# EPWR01.net
KiCad netlist of a schematic drawn in EAGLE
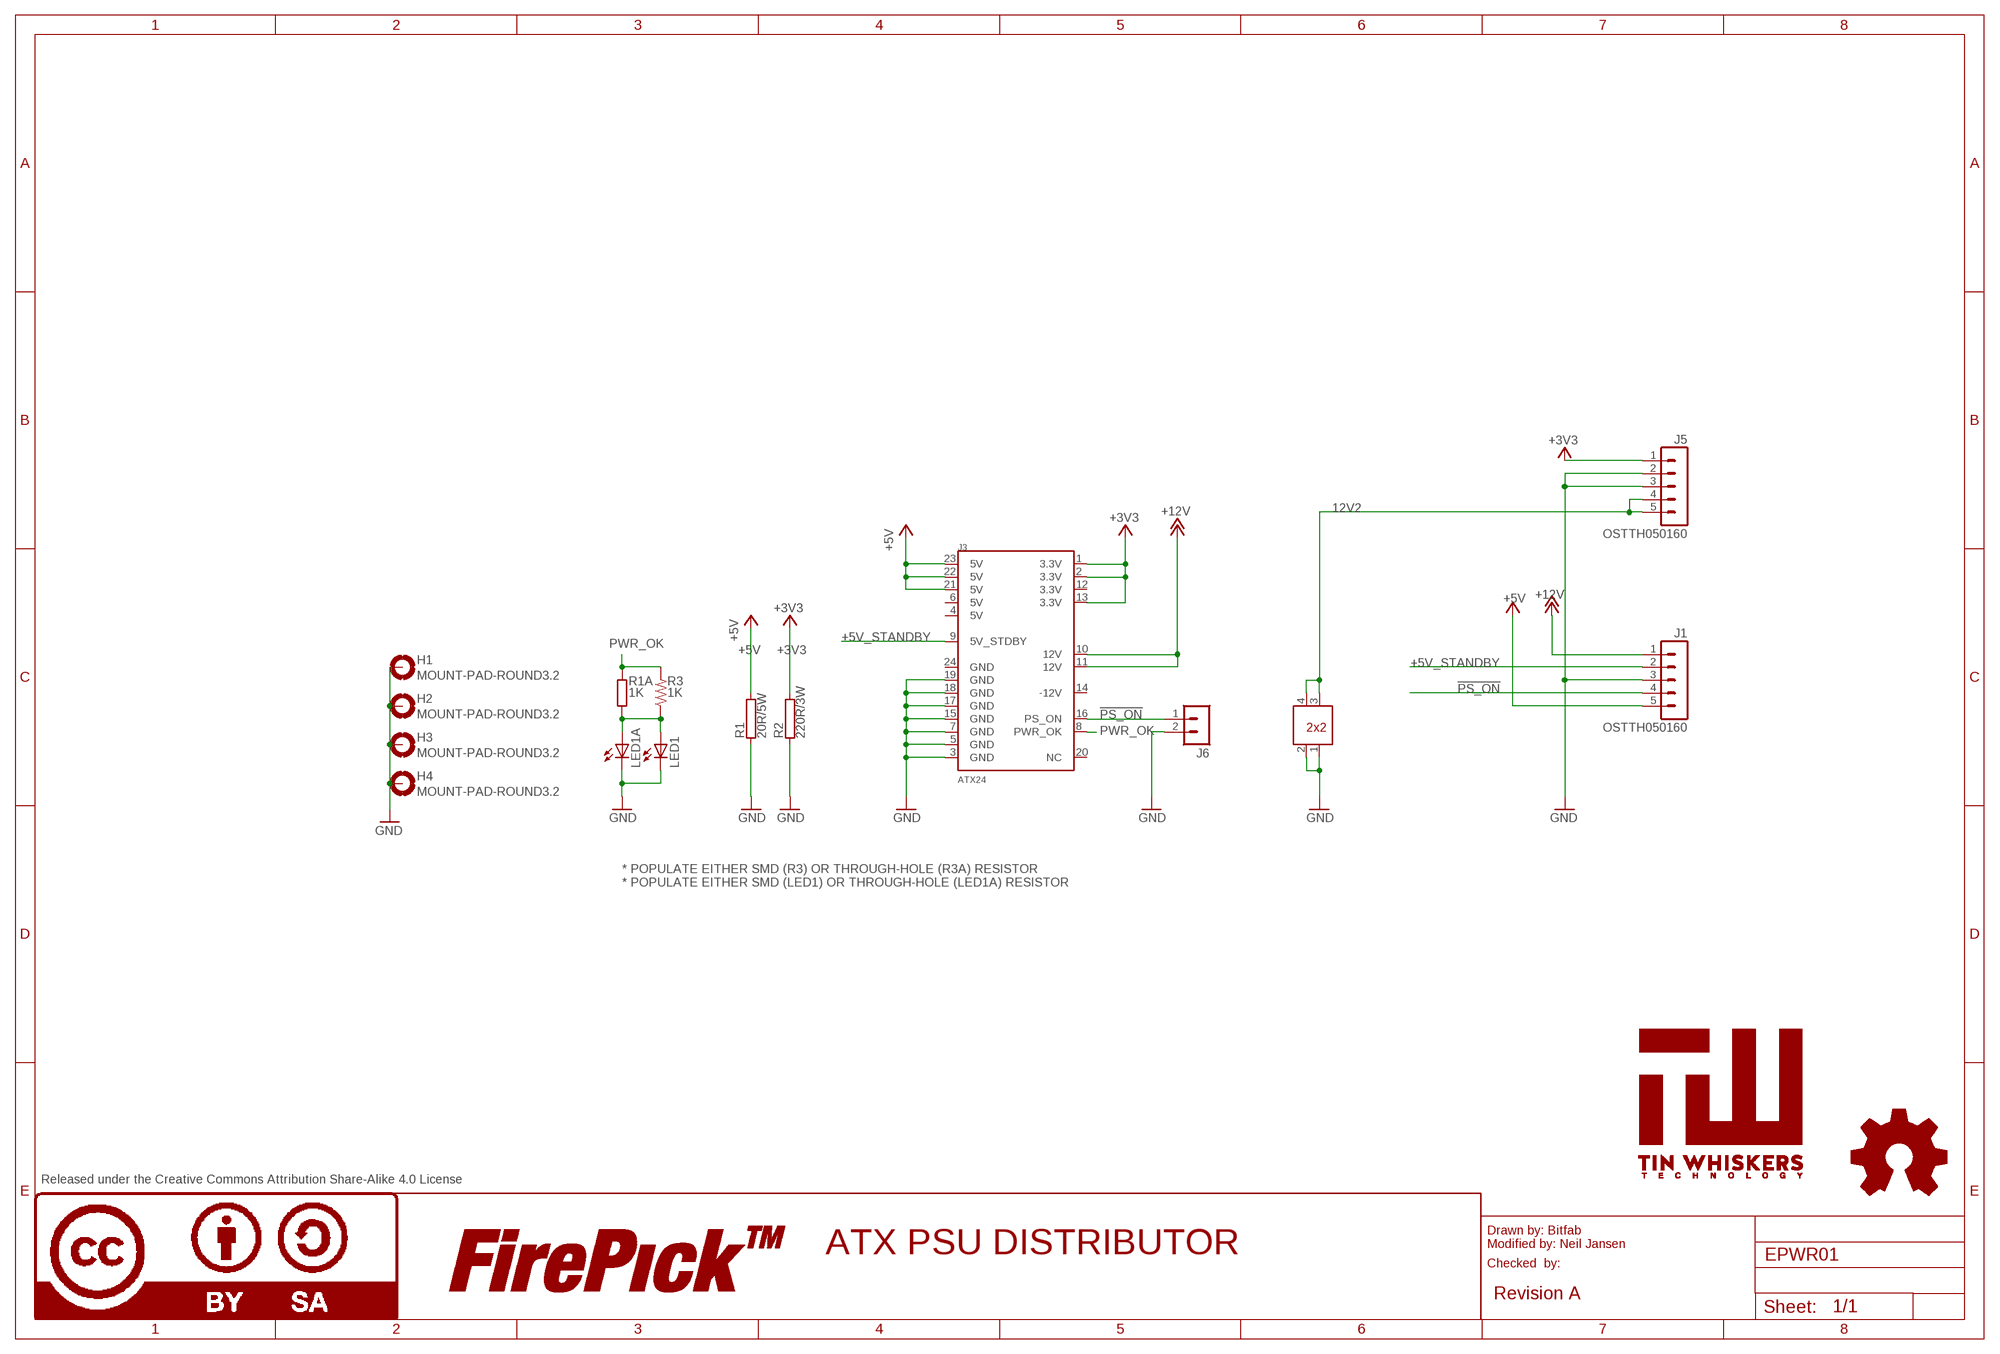
[diagram p0: schematic, sheet 1]

(export (version "E")
  (design (tool "Eeschema 10.0.6"))
  (components
    (comp (ref "H1")
      (value "MOUNT-PAD-ROUND3.2")
      (footprint "eagle-import:3,2-PAD")
      (libsource (lib "eagle-import") (part "MOUNT-PAD-ROUND3.2"))
    )
    (comp (ref "H2")
      (value "MOUNT-PAD-ROUND3.2")
      (footprint "eagle-import:3,2-PAD")
      (libsource (lib "eagle-import") (part "MOUNT-PAD-ROUND3.2"))
    )
    (comp (ref "H3")
      (value "MOUNT-PAD-ROUND3.2")
      (footprint "eagle-import:3,2-PAD")
      (libsource (lib "eagle-import") (part "MOUNT-PAD-ROUND3.2"))
    )
    (comp (ref "H4")
      (value "MOUNT-PAD-ROUND3.2")
      (footprint "eagle-import:3,2-PAD")
      (libsource (lib "eagle-import") (part "MOUNT-PAD-ROUND3.2"))
    )
    (comp (ref "J1")
      (value "OSTTH050160")
      (footprint "eagle-import:CONN-OSTTH050160")
      (libsource (lib "eagle-import") (part "CONN-OSTTH050160"))
    )
    (comp (ref "J3")
      (value "ATX24")
      (footprint "eagle-import:ATX24")
      (fields (field (name "PARTNO") "2-1586043-4"))
      (libsource (lib "eagle-import") (part "ATX24-REVERSIBLE"))
    )
    (comp (ref "J4")
      (value "ATX2X2")
      (footprint "eagle-import:ATX2X2")
      (fields (field (name "PARTNO") "1586041-4"))
      (libsource (lib "eagle-import") (part "ATX2X2"))
    )
    (comp (ref "J5")
      (value "OSTTH050160")
      (footprint "eagle-import:CONN-OSTTH050160")
      (libsource (lib "eagle-import") (part "CONN-OSTTH050160"))
    )
    (comp (ref "J6")
      (value "MA02-1")
      (footprint "eagle-import:MA02-1")
      (fields (field (name "PARTNO") "CONN-0.1-RA-1X2"))
      (libsource (lib "eagle-import") (part "MA02-1"))
    )
    (comp (ref "LED1")
      (value "LED1206")
      (footprint "eagle-import:LED-1206")
      (fields (field (name "PARTNO") "LTST-C150AKT"))
      (libsource (lib "eagle-import") (part "LED1206"))
    )
    (comp (ref "LED1A")
      (value "LED3MM")
      (footprint "eagle-import:LED3MM")
      (libsource (lib "eagle-import") (part "led_LED3MM"))
    )
    (comp (ref "LOGO4")
      (value "LOGO-FIREPICKLARGE")
      (footprint "eagle-import:LOGO-FIREPICK")
      (libsource (lib "eagle-import") (part "LOGO-FIREPICKLARGE"))
    )
    (comp (ref "LOGO5")
      (value "LOGO-OSHWMEDIUM")
      (footprint "eagle-import:LOGO-OSHW-MEDIUM")
      (libsource (lib "eagle-import") (part "LOGO-OSHWMEDIUM"))
    )
    (comp (ref "LOGO6")
      (value "LOGO-CC-BY-SALARGE")
      (footprint "eagle-import:LOGO-CC-BY-SA")
      (libsource (lib "eagle-import") (part "LOGO-CC-BY-SALARGE"))
    )
    (comp (ref "R1")
      (value "20R/5W")
      (footprint "eagle-import:HPS923")
      (fields (field (name "PARTNO") "SQP500JB-20R"))
      (libsource (lib "eagle-import") (part "RHPS923"))
    )
    (comp (ref "R1A")
      (value "1K")
      (footprint "eagle-import:0207_10")
      (libsource (lib "eagle-import") (part "R-EU_0207/10"))
    )
    (comp (ref "R2")
      (value "220R/3W")
      (footprint "eagle-import:CA4050")
      (fields (field (name "PARTNO") "PNP3WVJR-73-220R"))
      (libsource (lib "eagle-import") (part "RCA4050"))
    )
    (comp (ref "R3")
      (value "1K")
      (footprint "eagle-import:0805")
      (fields (field (name "PARTNO") "RC0805FR-071KL"))
      (libsource (lib "eagle-import") (part "RESISTOR0805-RES"))
    )
    (comp (ref "U$1")
      (value "TIN-WHISKERSSMALL")
      (footprint "eagle-import:TIN-WHISKERS-SMALL")
      (libsource (lib "eagle-import") (part "TIN-WHISKERSSMALL"))
    )
  )
  (nets
    (net (code "1") (name "+3V3") (class "Default")
      (node (ref "J3") (pin "1") (pinfunction "3.3V_1") (pintype "bidirectional"))
      (node (ref "J3") (pin "13") (pinfunction "3.3V_13") (pintype "bidirectional"))
      (node (ref "J3") (pin "2") (pinfunction "3.3V_2") (pintype "bidirectional"))
      (node (ref "J5") (pin "1") (pinfunction "1_1") (pintype "passive"))
      (node (ref "R2") (pin "2") (pinfunction "2_2") (pintype "passive"))
    )
    (net (code "2") (name "+5V") (class "Default")
      (node (ref "J1") (pin "5") (pinfunction "5_5") (pintype "passive"))
      (node (ref "J3") (pin "21") (pinfunction "5V_21") (pintype "bidirectional"))
      (node (ref "J3") (pin "22") (pinfunction "5V_22") (pintype "bidirectional"))
      (node (ref "J3") (pin "23") (pinfunction "5V_23") (pintype "bidirectional"))
      (node (ref "R1") (pin "2") (pinfunction "2_2") (pintype "passive"))
    )
    (net (code "3") (name "+12V") (class "Default")
      (node (ref "J1") (pin "1") (pinfunction "1_1") (pintype "passive"))
      (node (ref "J3") (pin "10") (pinfunction "12V_10") (pintype "bidirectional"))
      (node (ref "J3") (pin "11") (pinfunction "12V_11") (pintype "bidirectional"))
    )
    (net (code "4") (name "/+5V_STANDBY") (class "Default")
      (node (ref "J1") (pin "2") (pinfunction "2_2") (pintype "passive"))
      (node (ref "J3") (pin "9") (pinfunction "5V_STDBY_9") (pintype "bidirectional"))
    )
    (net (code "5") (name "/12V2") (class "Default")
      (node (ref "J4") (pin "3") (pinfunction "P$3_3") (pintype "bidirectional"))
      (node (ref "J4") (pin "4") (pinfunction "P$4_4") (pintype "bidirectional"))
      (node (ref "J5") (pin "4") (pinfunction "4_4") (pintype "passive"))
      (node (ref "J5") (pin "5") (pinfunction "5_5") (pintype "passive"))
    )
    (net (code "6") (name "/PWR_OK") (class "Default")
      (node (ref "J3") (pin "8") (pinfunction "PWR_OK_8") (pintype "bidirectional"))
      (node (ref "R1A") (pin "2") (pinfunction "2_2") (pintype "passive"))
      (node (ref "R3") (pin "2") (pinfunction "2_2") (pintype "passive"))
    )
    (net (code "7") (name "/~{PS_ON}") (class "Default")
      (node (ref "J1") (pin "4") (pinfunction "4_4") (pintype "passive"))
      (node (ref "J3") (pin "16") (pinfunction "PS_ON_16") (pintype "bidirectional"))
      (node (ref "J6") (pin "1") (pinfunction "1_1") (pintype "passive"))
    )
    (net (code "8") (name "GND") (class "Default")
      (node (ref "H1") (pin "B3,2") (pinfunction "MOUNT_B3,2") (pintype "passive"))
      (node (ref "H2") (pin "B3,2") (pinfunction "MOUNT_B3,2") (pintype "passive"))
      (node (ref "H3") (pin "B3,2") (pinfunction "MOUNT_B3,2") (pintype "passive"))
      (node (ref "H4") (pin "B3,2") (pinfunction "MOUNT_B3,2") (pintype "passive"))
      (node (ref "J1") (pin "3") (pinfunction "3_3") (pintype "passive"))
      (node (ref "J3") (pin "15") (pinfunction "GND_15") (pintype "bidirectional"))
      (node (ref "J3") (pin "17") (pinfunction "GND_17") (pintype "bidirectional"))
      (node (ref "J3") (pin "18") (pinfunction "GND_18") (pintype "bidirectional"))
      (node (ref "J3") (pin "19") (pinfunction "GND_19") (pintype "bidirectional"))
      (node (ref "J3") (pin "3") (pinfunction "GND_3") (pintype "bidirectional"))
      (node (ref "J3") (pin "5") (pinfunction "GND_5") (pintype "bidirectional"))
      (node (ref "J3") (pin "7") (pinfunction "GND_7") (pintype "bidirectional"))
      (node (ref "J4") (pin "1") (pinfunction "P$1_1") (pintype "bidirectional"))
      (node (ref "J4") (pin "2") (pinfunction "P$2_2") (pintype "bidirectional"))
      (node (ref "J5") (pin "2") (pinfunction "2_2") (pintype "passive"))
      (node (ref "J5") (pin "3") (pinfunction "3_3") (pintype "passive"))
      (node (ref "J6") (pin "2") (pinfunction "2_2") (pintype "passive"))
      (node (ref "LED1") (pin "C") (pinfunction "C_C") (pintype "passive"))
      (node (ref "LED1A") (pin "K") (pinfunction "C_K") (pintype "passive"))
      (node (ref "R1") (pin "1") (pinfunction "1_1") (pintype "passive"))
      (node (ref "R2") (pin "1") (pinfunction "1_1") (pintype "passive"))
    )
    (net (code "9") (name "Net-(LED1-PadA)") (class "Default")
      (node (ref "LED1") (pin "A") (pinfunction "A_A") (pintype "passive"))
      (node (ref "LED1A") (pin "A") (pinfunction "A_A") (pintype "passive"))
      (node (ref "R1A") (pin "1") (pinfunction "1_1") (pintype "passive"))
      (node (ref "R3") (pin "1") (pinfunction "1_1") (pintype "passive"))
    )
    (net (code "10") (name "unconnected-(J3--12V-Pad14)") (class "Default")
      (node (ref "J3") (pin "14") (pinfunction "-12V_14") (pintype "bidirectional"))
    )
    (net (code "11") (name "unconnected-(J3-3.3V-Pad12)") (class "Default")
      (node (ref "J3") (pin "12") (pinfunction "3.3V_12") (pintype "bidirectional"))
    )
    (net (code "12") (name "unconnected-(J3-5V-Pad4)") (class "Default")
      (node (ref "J3") (pin "4") (pinfunction "5V_4") (pintype "bidirectional"))
    )
    (net (code "13") (name "unconnected-(J3-5V-Pad6)") (class "Default")
      (node (ref "J3") (pin "6") (pinfunction "5V_6") (pintype "bidirectional"))
    )
    (net (code "14") (name "unconnected-(J3-GND-Pad24)") (class "Default")
      (node (ref "J3") (pin "24") (pinfunction "GND_24") (pintype "bidirectional"))
    )
    (net (code "15") (name "unconnected-(J3-NC-Pad20)") (class "Default")
      (node (ref "J3") (pin "20") (pinfunction "NC_20") (pintype "bidirectional"))
    )
  )
)
